# FumeDisperser.net
KiCad netlist of a schematic drawn in EAGLE
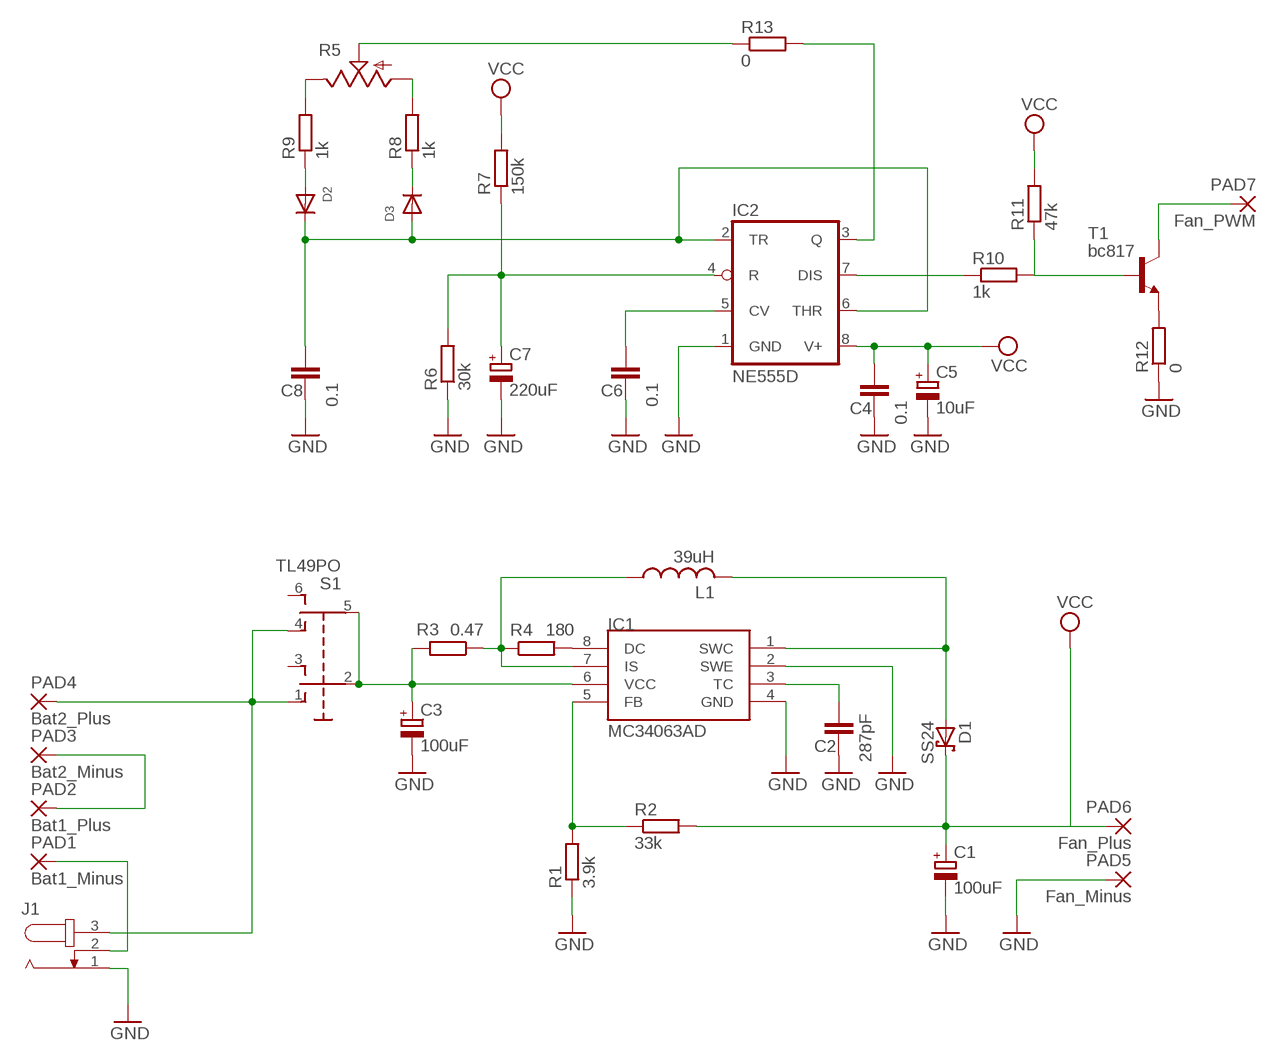
[diagram p0: schematic, sheet 1]

(export (version "E")
  (design (tool "Eeschema 10.0.6"))
  (components
    (comp (ref "C1")
      (value "100uF")
      (footprint "eagle-import:D_7343-31R")
      (libsource (lib "eagle-import") (part "CPOL-EUD/7343-31R"))
    )
    (comp (ref "C2")
      (value "287pF")
      (footprint "eagle-import:C1206")
      (libsource (lib "eagle-import") (part "C-EUC1206"))
    )
    (comp (ref "C3")
      (value "100uF")
      (footprint "eagle-import:D_7343-31R")
      (libsource (lib "eagle-import") (part "CPOL-EUD/7343-31R"))
    )
    (comp (ref "C4")
      (value "0.1")
      (footprint "eagle-import:C1206")
      (libsource (lib "eagle-import") (part "C-EUC1206"))
    )
    (comp (ref "C5")
      (value "10uF")
      (footprint "eagle-import:D_7343-31R")
      (libsource (lib "eagle-import") (part "CPOL-EUD/7343-31R"))
    )
    (comp (ref "C6")
      (value "0.1")
      (footprint "eagle-import:C1206")
      (libsource (lib "eagle-import") (part "C-EUC1206"))
    )
    (comp (ref "C7")
      (value "220uF")
      (footprint "eagle-import:D_7343-31R")
      (libsource (lib "eagle-import") (part "CPOL-EUD/7343-31R"))
    )
    (comp (ref "C8")
      (value "0.1")
      (footprint "eagle-import:C1206")
      (libsource (lib "eagle-import") (part "C-EUC1206"))
    )
    (comp (ref "D1")
      (value "SS24")
      (footprint "eagle-import:SMB")
      (libsource (lib "eagle-import") (part "SCHOTTKY-DIODESMD"))
    )
    (comp (ref "D2")
      (value "DIODESOD-123")
      (footprint "eagle-import:SOD-123")
      (libsource (lib "eagle-import") (part "DIODESOD-123"))
    )
    (comp (ref "D3")
      (value "DIODESOD-123")
      (footprint "eagle-import:SOD-123")
      (libsource (lib "eagle-import") (part "DIODESOD-123"))
    )
    (comp (ref "IC1")
      (value "MC34063AD")
      (footprint "eagle-import:SOIC8")
      (libsource (lib "eagle-import") (part "MC34063AD"))
    )
    (comp (ref "IC2")
      (value "NE555D")
      (footprint "eagle-import:SO08")
      (libsource (lib "eagle-import") (part "555DNE"))
    )
    (comp (ref "J1")
      (value "JACK-PLUG0")
      (footprint "eagle-import:SPC4077")
      (libsource (lib "eagle-import") (part "JACK-PLUG0"))
    )
    (comp (ref "L1")
      (value "39uH")
      (footprint "eagle-import:L3225P")
      (libsource (lib "eagle-import") (part "L-USL3225P"))
    )
    (comp (ref "PAD1")
      (value "Bat1_Minus")
      (footprint "eagle-import:SMD2,54-5,08")
      (libsource (lib "eagle-import") (part "SMD5"))
    )
    (comp (ref "PAD2")
      (value "Bat1_Plus")
      (footprint "eagle-import:SMD2,54-5,08")
      (libsource (lib "eagle-import") (part "SMD5"))
    )
    (comp (ref "PAD3")
      (value "Bat2_Minus")
      (footprint "eagle-import:SMD2,54-5,08")
      (libsource (lib "eagle-import") (part "SMD5"))
    )
    (comp (ref "PAD4")
      (value "Bat2_Plus")
      (footprint "eagle-import:SMD2,54-5,08")
      (libsource (lib "eagle-import") (part "SMD5"))
    )
    (comp (ref "PAD5")
      (value "Fan_Minus")
      (footprint "eagle-import:SMD2,54-5,08")
      (libsource (lib "eagle-import") (part "SMD5"))
    )
    (comp (ref "PAD6")
      (value "Fan_Plus")
      (footprint "eagle-import:SMD2,54-5,08")
      (libsource (lib "eagle-import") (part "SMD5"))
    )
    (comp (ref "PAD7")
      (value "Fan_PWM")
      (footprint "eagle-import:SMD2,54-5,08")
      (libsource (lib "eagle-import") (part "SMD5"))
    )
    (comp (ref "R1")
      (value "3.9k")
      (footprint "eagle-import:M1206")
      (libsource (lib "eagle-import") (part "R-EU_M1206"))
    )
    (comp (ref "R2")
      (value "33k")
      (footprint "eagle-import:M1206")
      (libsource (lib "eagle-import") (part "R-EU_M1206"))
    )
    (comp (ref "R3")
      (value "0.47")
      (footprint "eagle-import:M1206")
      (libsource (lib "eagle-import") (part "R-EU_M1206"))
    )
    (comp (ref "R4")
      (value "180")
      (footprint "eagle-import:M1206")
      (libsource (lib "eagle-import") (part "R-EU_M1206"))
    )
    (comp (ref "R5")
      (value "US-EVUF2A")
      (footprint "eagle-import:EVUF")
      (libsource (lib "eagle-import") (part "US-EVUAF2"))
    )
    (comp (ref "R6")
      (value "30k")
      (footprint "eagle-import:M1206")
      (libsource (lib "eagle-import") (part "R-EU_M1206"))
    )
    (comp (ref "R7")
      (value "150k")
      (footprint "eagle-import:M1206")
      (libsource (lib "eagle-import") (part "R-EU_M1206"))
    )
    (comp (ref "R8")
      (value "1k")
      (footprint "eagle-import:M1206")
      (libsource (lib "eagle-import") (part "R-EU_M1206"))
    )
    (comp (ref "R9")
      (value "1k")
      (footprint "eagle-import:M1206")
      (libsource (lib "eagle-import") (part "R-EU_M1206"))
    )
    (comp (ref "R10")
      (value "1k")
      (footprint "eagle-import:M1206")
      (libsource (lib "eagle-import") (part "R-EU_M1206"))
    )
    (comp (ref "R11")
      (value "47k")
      (footprint "eagle-import:M1206")
      (libsource (lib "eagle-import") (part "R-EU_M1206"))
    )
    (comp (ref "R12")
      (value "0")
      (footprint "eagle-import:M1206")
      (libsource (lib "eagle-import") (part "R-EU_M1206"))
    )
    (comp (ref "R13")
      (value "0")
      (footprint "eagle-import:M1206")
      (libsource (lib "eagle-import") (part "R-EU_M1206"))
    )
    (comp (ref "S1")
      (value "TL49PO")
      (footprint "eagle-import:TL4XPO")
      (libsource (lib "eagle-import") (part "TL49PO"))
    )
    (comp (ref "T1")
      (value "bc817")
      (footprint "eagle-import:SOT23-BEC")
      (libsource (lib "eagle-import") (part "-NPN-SOT23-BECBC817-16"))
    )
  )
  (nets
    (net (code "1") (name "GND") (class "Default")
      (node (ref "C1") (pin "-") (pinfunction "-_-") (pintype "passive"))
      (node (ref "C2") (pin "2") (pinfunction "2_2") (pintype "passive"))
      (node (ref "C3") (pin "-") (pinfunction "-_-") (pintype "passive"))
      (node (ref "C4") (pin "2") (pinfunction "2_2") (pintype "passive"))
      (node (ref "C5") (pin "-") (pinfunction "-_-") (pintype "passive"))
      (node (ref "C6") (pin "2") (pinfunction "2_2") (pintype "passive"))
      (node (ref "C7") (pin "-") (pinfunction "-_-") (pintype "passive"))
      (node (ref "C8") (pin "2") (pinfunction "2_2") (pintype "passive"))
      (node (ref "IC1") (pin "2") (pinfunction "SWE_2") (pintype "passive"))
      (node (ref "IC1") (pin "4") (pinfunction "GND_4") (pintype "passive"))
      (node (ref "IC2") (pin "1") (pinfunction "GND_1") (pintype "power_in"))
      (node (ref "J1") (pin "1") (pinfunction "1_1") (pintype "passive"))
      (node (ref "PAD5") (pin "1") (pinfunction "P_1") (pintype "passive"))
      (node (ref "R1") (pin "1") (pinfunction "1_1") (pintype "passive"))
      (node (ref "R12") (pin "1") (pinfunction "1_1") (pintype "passive"))
      (node (ref "R6") (pin "1") (pinfunction "1_1") (pintype "passive"))
    )
    (net (code "2") (name "Net-(D2-PadA)") (class "Default")
      (node (ref "D2") (pin "A") (pinfunction "A_A") (pintype "passive"))
      (node (ref "R9") (pin "1") (pinfunction "1_1") (pintype "passive"))
    )
    (net (code "3") (name "Net-(D3-PadC)") (class "Default")
      (node (ref "D3") (pin "C") (pinfunction "C_C") (pintype "passive"))
      (node (ref "R8") (pin "1") (pinfunction "1_1") (pintype "passive"))
    )
    (net (code "4") (name "Net-(IC1-DC)") (class "Default")
      (node (ref "IC1") (pin "8") (pinfunction "DC_8") (pintype "passive"))
      (node (ref "R4") (pin "2") (pinfunction "2_2") (pintype "passive"))
    )
    (net (code "5") (name "Net-(IC1-FB)") (class "Default")
      (node (ref "IC1") (pin "5") (pinfunction "FB_5") (pintype "passive"))
      (node (ref "R1") (pin "2") (pinfunction "2_2") (pintype "passive"))
      (node (ref "R2") (pin "1") (pinfunction "1_1") (pintype "passive"))
    )
    (net (code "6") (name "Net-(IC1-IS)") (class "Default")
      (node (ref "IC1") (pin "7") (pinfunction "IS_7") (pintype "passive"))
      (node (ref "L1") (pin "1") (pinfunction "1_1") (pintype "passive"))
      (node (ref "R3") (pin "1") (pinfunction "1_1") (pintype "passive"))
      (node (ref "R4") (pin "1") (pinfunction "1_1") (pintype "passive"))
    )
    (net (code "7") (name "Net-(IC1-SWC)") (class "Default")
      (node (ref "D1") (pin "A") (pinfunction "A_A") (pintype "passive"))
      (node (ref "IC1") (pin "1") (pinfunction "SWC_1") (pintype "passive"))
      (node (ref "L1") (pin "2") (pinfunction "2_2") (pintype "passive"))
    )
    (net (code "8") (name "Net-(IC1-TC)") (class "Default")
      (node (ref "C2") (pin "1") (pinfunction "1_1") (pintype "passive"))
      (node (ref "IC1") (pin "3") (pinfunction "TC_3") (pintype "passive"))
    )
    (net (code "9") (name "Net-(IC1-VCC)") (class "Default")
      (node (ref "C3") (pin "+") (pinfunction "+_+") (pintype "passive"))
      (node (ref "IC1") (pin "6") (pinfunction "VCC_6") (pintype "passive"))
      (node (ref "R3") (pin "2") (pinfunction "2_2") (pintype "passive"))
      (node (ref "S1") (pin "2") (pinfunction "P_2") (pintype "passive"))
      (node (ref "S1") (pin "5") (pinfunction "P1_5") (pintype "passive"))
    )
    (net (code "10") (name "Net-(IC2-CV)") (class "Default")
      (node (ref "C6") (pin "1") (pinfunction "1_1") (pintype "passive"))
      (node (ref "IC2") (pin "5") (pinfunction "CV_5") (pintype "input"))
    )
    (net (code "11") (name "Net-(IC2-DIS)") (class "Default")
      (node (ref "IC2") (pin "7") (pinfunction "DIS_7") (pintype "input"))
      (node (ref "R10") (pin "1") (pinfunction "1_1") (pintype "passive"))
    )
    (net (code "12") (name "Net-(IC2-Q)") (class "Default")
      (node (ref "IC2") (pin "3") (pinfunction "Q_3") (pintype "output"))
      (node (ref "R13") (pin "2") (pinfunction "2_2") (pintype "passive"))
    )
    (net (code "13") (name "Net-(IC2-R)") (class "Default")
      (node (ref "C7") (pin "+") (pinfunction "+_+") (pintype "passive"))
      (node (ref "IC2") (pin "4") (pinfunction "R_4") (pintype "input"))
      (node (ref "R6") (pin "2") (pinfunction "2_2") (pintype "passive"))
      (node (ref "R7") (pin "1") (pinfunction "1_1") (pintype "passive"))
    )
    (net (code "14") (name "Net-(IC2-THR)") (class "Default")
      (node (ref "C8") (pin "1") (pinfunction "1_1") (pintype "passive"))
      (node (ref "D2") (pin "C") (pinfunction "C_C") (pintype "passive"))
      (node (ref "D3") (pin "A") (pinfunction "A_A") (pintype "passive"))
      (node (ref "IC2") (pin "2") (pinfunction "TR_2") (pintype "input"))
      (node (ref "IC2") (pin "6") (pinfunction "THR_6") (pintype "input"))
    )
    (net (code "15") (name "Net-(PAD1-P)") (class "Default")
      (node (ref "J1") (pin "2") (pinfunction "2_2") (pintype "passive"))
      (node (ref "PAD1") (pin "1") (pinfunction "P_1") (pintype "passive"))
    )
    (net (code "16") (name "Net-(PAD2-P)") (class "Default")
      (node (ref "PAD2") (pin "1") (pinfunction "P_1") (pintype "passive"))
      (node (ref "PAD3") (pin "1") (pinfunction "P_1") (pintype "passive"))
    )
    (net (code "17") (name "Net-(PAD4-P)") (class "Default")
      (node (ref "J1") (pin "3") (pinfunction "3_3") (pintype "passive"))
      (node (ref "PAD4") (pin "1") (pinfunction "P_1") (pintype "passive"))
      (node (ref "S1") (pin "1") (pinfunction "O_1") (pintype "passive"))
      (node (ref "S1") (pin "4") (pinfunction "O1_4") (pintype "passive"))
    )
    (net (code "18") (name "Net-(PAD7-P)") (class "Default")
      (node (ref "PAD7") (pin "1") (pinfunction "P_1") (pintype "passive"))
      (node (ref "T1") (pin "C") (pinfunction "C_C") (pintype "passive"))
    )
    (net (code "19") (name "Net-(R5-A)") (class "Default")
      (node (ref "R5") (pin "1") (pinfunction "A_1") (pintype "passive"))
      (node (ref "R8") (pin "2") (pinfunction "2_2") (pintype "passive"))
    )
    (net (code "20") (name "Net-(R5-E)") (class "Default")
      (node (ref "R5") (pin "3") (pinfunction "E_3") (pintype "passive"))
      (node (ref "R9") (pin "2") (pinfunction "2_2") (pintype "passive"))
    )
    (net (code "21") (name "Net-(R5-S)") (class "Default")
      (node (ref "R13") (pin "1") (pinfunction "1_1") (pintype "passive"))
      (node (ref "R5") (pin "2") (pinfunction "S_2") (pintype "passive"))
    )
    (net (code "22") (name "Net-(R10-Pad2)") (class "Default")
      (node (ref "R10") (pin "2") (pinfunction "2_2") (pintype "passive"))
      (node (ref "R11") (pin "1") (pinfunction "1_1") (pintype "passive"))
      (node (ref "T1") (pin "B") (pinfunction "B_B") (pintype "passive"))
    )
    (net (code "23") (name "Net-(R12-Pad2)") (class "Default")
      (node (ref "R12") (pin "2") (pinfunction "2_2") (pintype "passive"))
      (node (ref "T1") (pin "E") (pinfunction "E_E") (pintype "passive"))
    )
    (net (code "24") (name "VCC") (class "Default")
      (node (ref "C1") (pin "+") (pinfunction "+_+") (pintype "passive"))
      (node (ref "C4") (pin "1") (pinfunction "1_1") (pintype "passive"))
      (node (ref "C5") (pin "+") (pinfunction "+_+") (pintype "passive"))
      (node (ref "D1") (pin "C") (pinfunction "C_C") (pintype "passive"))
      (node (ref "IC2") (pin "8") (pinfunction "V+_8") (pintype "power_in"))
      (node (ref "PAD6") (pin "1") (pinfunction "P_1") (pintype "passive"))
      (node (ref "R11") (pin "2") (pinfunction "2_2") (pintype "passive"))
      (node (ref "R2") (pin "2") (pinfunction "2_2") (pintype "passive"))
      (node (ref "R7") (pin "2") (pinfunction "2_2") (pintype "passive"))
    )
    (net (code "25") (name "unconnected-(S1-S-Pad3)") (class "Default")
      (node (ref "S1") (pin "3") (pinfunction "S_3") (pintype "passive"))
    )
    (net (code "26") (name "unconnected-(S1-S1-Pad6)") (class "Default")
      (node (ref "S1") (pin "6") (pinfunction "S1_6") (pintype "passive"))
    )
  )
)
